# Schematic.net
KiCad netlist of a schematic drawn in Altium Designer
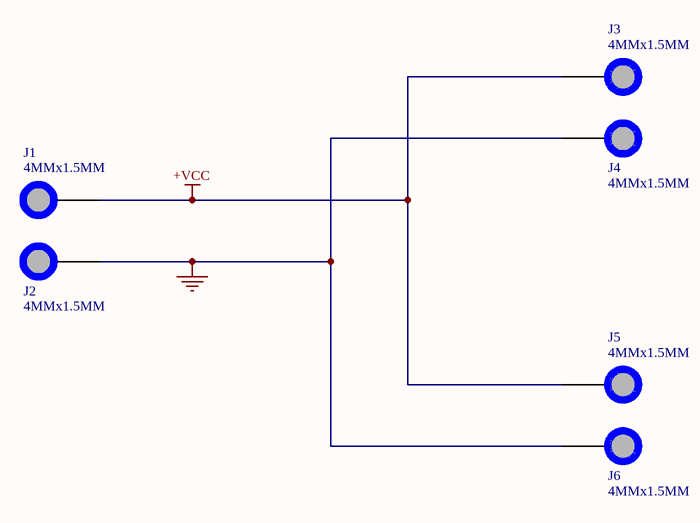
[diagram p0: Schematic.SchDoc]

(export (version "E")
  (design (tool "Eeschema 10.0.6"))
  (components
    (comp (ref "J1")
      (value "4MMx1.5MM")
      (footprint "PAD_WITH_HOLE_4MMx1MM5")
      (description "Pad with a hole 4mm x 1.5mm")
      (libsource (lib "SchLib") (part "PAD_WITH_HOLE_4MMx1MM5"))
    )
    (comp (ref "J2")
      (value "4MMx1.5MM")
      (footprint "PAD_WITH_HOLE_4MMx1MM5")
      (description "Pad with a hole 4mm x 1.5mm")
      (libsource (lib "SchLib") (part "PAD_WITH_HOLE_4MMx1MM5"))
    )
    (comp (ref "J3")
      (value "4MMx1.5MM")
      (footprint "PAD_WITH_HOLE_4MMx1MM5")
      (description "Pad with a hole 4mm x 1.5mm")
      (libsource (lib "SchLib") (part "PAD_WITH_HOLE_4MMx1MM5"))
    )
    (comp (ref "J4")
      (value "4MMx1.5MM")
      (footprint "PAD_WITH_HOLE_4MMx1MM5")
      (description "Pad with a hole 4mm x 1.5mm")
      (libsource (lib "SchLib") (part "PAD_WITH_HOLE_4MMx1MM5"))
    )
    (comp (ref "J5")
      (value "4MMx1.5MM")
      (footprint "PAD_WITH_HOLE_4MMx1MM5")
      (description "Pad with a hole 4mm x 1.5mm")
      (libsource (lib "SchLib") (part "PAD_WITH_HOLE_4MMx1MM5"))
    )
    (comp (ref "J6")
      (value "4MMx1.5MM")
      (footprint "PAD_WITH_HOLE_4MMx1MM5")
      (description "Pad with a hole 4mm x 1.5mm")
      (libsource (lib "SchLib") (part "PAD_WITH_HOLE_4MMx1MM5"))
    )
  )
  (nets
    (net (code "1") (name "+VCC") (class "Default")
      (node (ref "J1") (pin "1") (pinfunction "1_1") (pintype "passive"))
      (node (ref "J3") (pin "1") (pinfunction "1_1") (pintype "passive"))
      (node (ref "J5") (pin "1") (pinfunction "1_1") (pintype "passive"))
    )
    (net (code "2") (name "GND") (class "Default")
      (node (ref "J2") (pin "1") (pinfunction "1_1") (pintype "passive"))
      (node (ref "J4") (pin "1") (pinfunction "1_1") (pintype "passive"))
      (node (ref "J6") (pin "1") (pinfunction "1_1") (pintype "passive"))
    )
  )
)
